# display_schematic.net
KiCad netlist of a schematic drawn in EAGLE
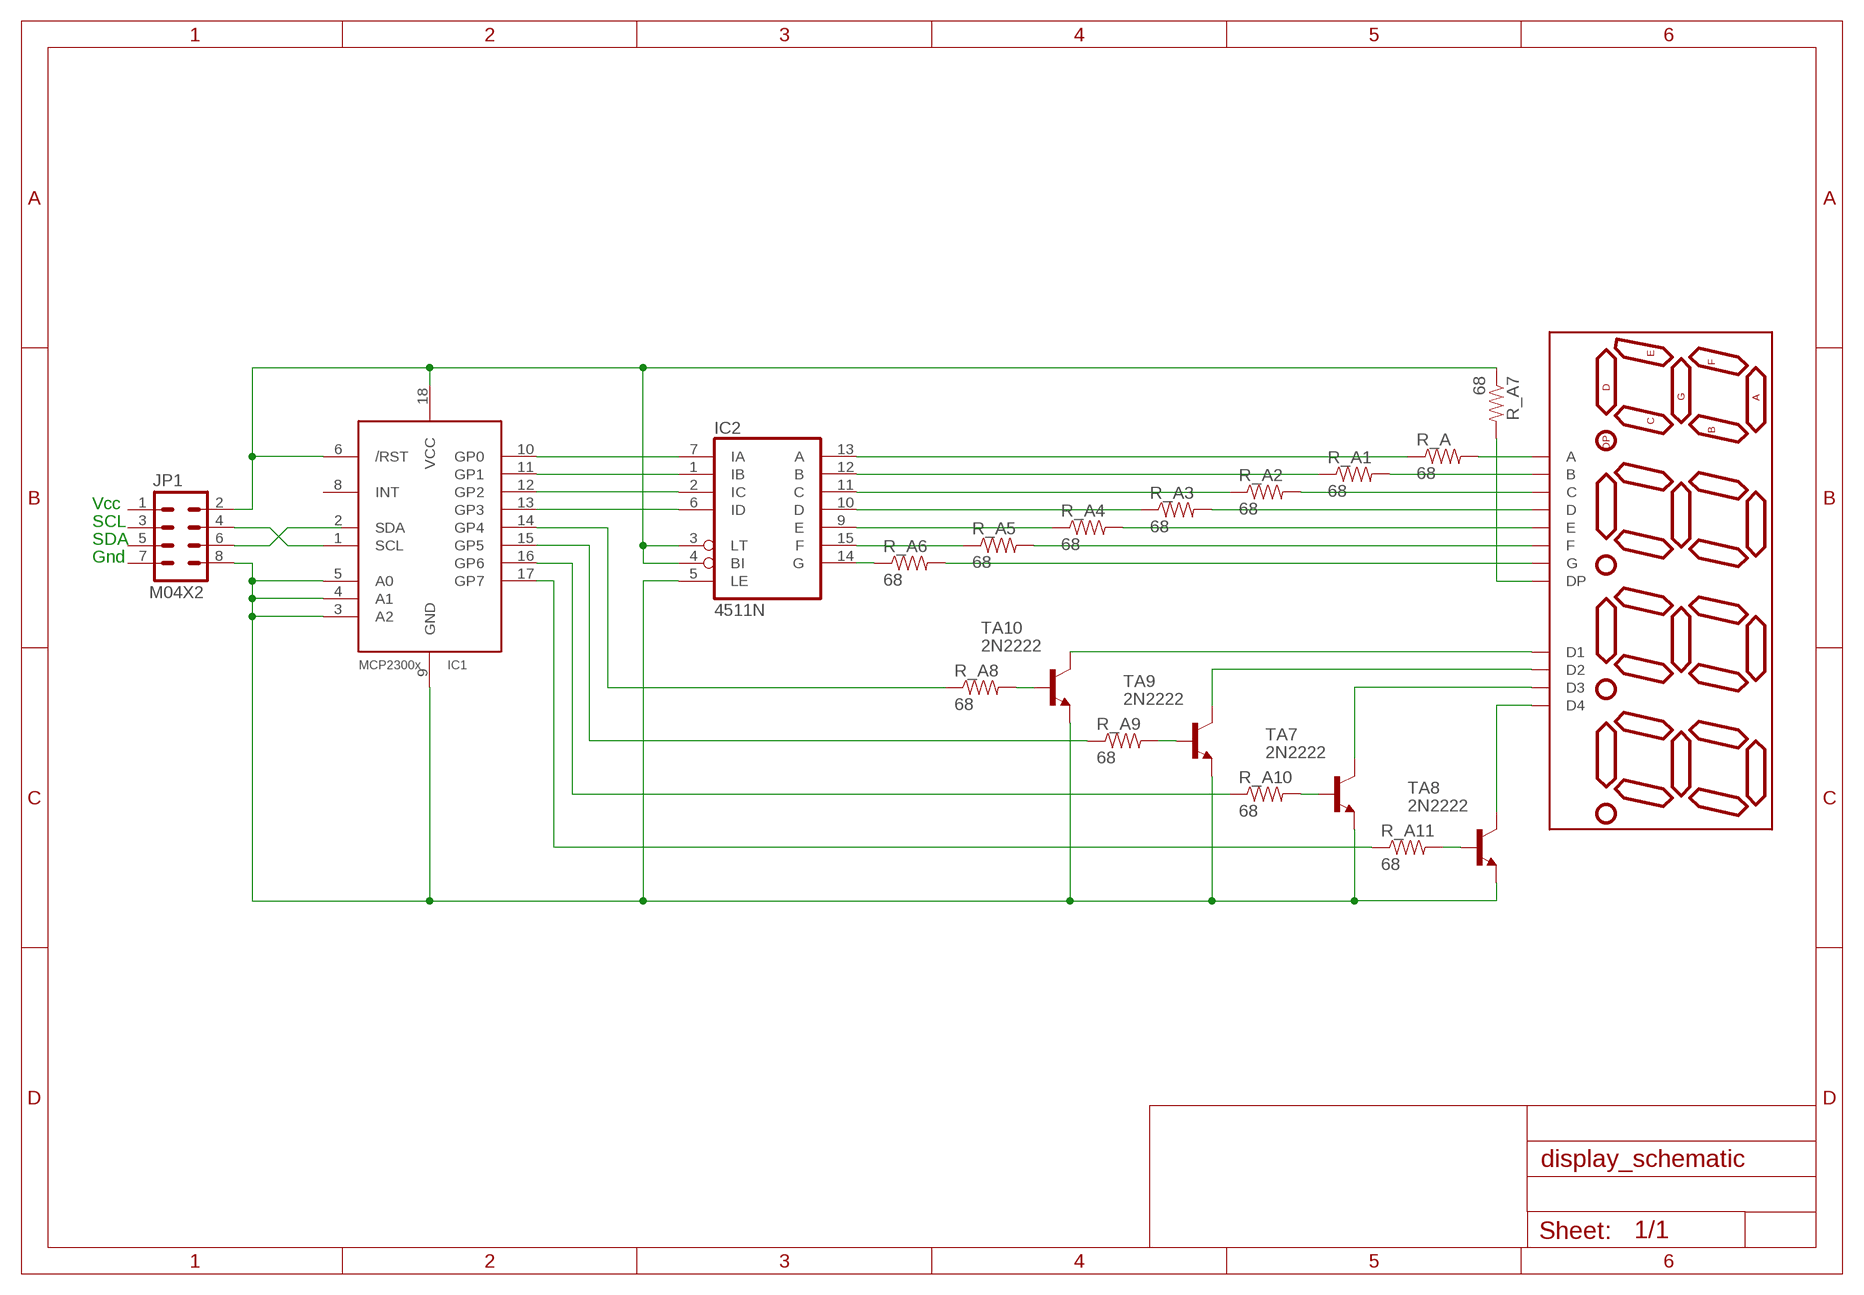
[diagram p0: schematic, sheet 1]

(export (version "E")
  (design (tool "Eeschema 10.0.6"))
  (components
    (comp (ref "DISPLAY7S4D1")
      (value "7SEG-4DIG-NEW")
      (footprint "eagle-import:7SEG-4DIG-NEW")
      (libsource (lib "eagle-import") (part "7SEG-4DIG-NEW"))
    )
    (comp (ref "IC1")
      (value "MCP2300X/P")
      (footprint "eagle-import:DIL18")
      (libsource (lib "eagle-import") (part "MCP2300X/P"))
    )
    (comp (ref "IC2")
      (value "4511N")
      (footprint "eagle-import:DIL16")
      (libsource (lib "eagle-import") (part "4511N"))
    )
    (comp (ref "JP1")
      (value "M04X2")
      (footprint "eagle-import:2X4")
      (libsource (lib "eagle-import") (part "M04X2"))
    )
    (comp (ref "R_A")
      (value "68")
      (footprint "eagle-import:AXIAL-0.3")
      (libsource (lib "eagle-import") (part "RESISTORAXIAL-0.3"))
    )
    (comp (ref "R_A1")
      (value "68")
      (footprint "eagle-import:AXIAL-0.3")
      (libsource (lib "eagle-import") (part "RESISTORAXIAL-0.3"))
    )
    (comp (ref "R_A2")
      (value "68")
      (footprint "eagle-import:AXIAL-0.3")
      (libsource (lib "eagle-import") (part "RESISTORAXIAL-0.3"))
    )
    (comp (ref "R_A3")
      (value "68")
      (footprint "eagle-import:AXIAL-0.3")
      (libsource (lib "eagle-import") (part "RESISTORAXIAL-0.3"))
    )
    (comp (ref "R_A4")
      (value "68")
      (footprint "eagle-import:AXIAL-0.3")
      (libsource (lib "eagle-import") (part "RESISTORAXIAL-0.3"))
    )
    (comp (ref "R_A5")
      (value "68")
      (footprint "eagle-import:AXIAL-0.3")
      (libsource (lib "eagle-import") (part "RESISTORAXIAL-0.3"))
    )
    (comp (ref "R_A6")
      (value "68")
      (footprint "eagle-import:AXIAL-0.3")
      (libsource (lib "eagle-import") (part "RESISTORAXIAL-0.3"))
    )
    (comp (ref "R_A7")
      (value "68")
      (footprint "eagle-import:AXIAL-0.3")
      (libsource (lib "eagle-import") (part "RESISTORAXIAL-0.3"))
    )
    (comp (ref "R_A8")
      (value "68")
      (footprint "eagle-import:AXIAL-0.3")
      (libsource (lib "eagle-import") (part "RESISTORAXIAL-0.3"))
    )
    (comp (ref "R_A9")
      (value "68")
      (footprint "eagle-import:AXIAL-0.3")
      (libsource (lib "eagle-import") (part "RESISTORAXIAL-0.3"))
    )
    (comp (ref "R_A10")
      (value "68")
      (footprint "eagle-import:AXIAL-0.3")
      (libsource (lib "eagle-import") (part "RESISTORAXIAL-0.3"))
    )
    (comp (ref "R_A11")
      (value "68")
      (footprint "eagle-import:AXIAL-0.3")
      (libsource (lib "eagle-import") (part "RESISTORAXIAL-0.3"))
    )
    (comp (ref "TA7")
      (value "2N2222")
      (footprint "eagle-import:TO92-EBC-OVAL")
      (libsource (lib "eagle-import") (part "2N2222"))
    )
    (comp (ref "TA8")
      (value "2N2222")
      (footprint "eagle-import:TO92-EBC-OVAL")
      (libsource (lib "eagle-import") (part "2N2222"))
    )
    (comp (ref "TA9")
      (value "2N2222")
      (footprint "eagle-import:TO92-EBC-OVAL")
      (libsource (lib "eagle-import") (part "2N2222"))
    )
    (comp (ref "TA10")
      (value "2N2222")
      (footprint "eagle-import:TO92-EBC-OVAL")
      (libsource (lib "eagle-import") (part "2N2222"))
    )
  )
  (nets
    (net (code "1") (name "Net-(DISPLAY7S4D1-A)") (class "Default")
      (node (ref "DISPLAY7S4D1") (pin "11") (pinfunction "A_11") (pintype "bidirectional"))
      (node (ref "R_A") (pin "P$2") (pinfunction "2_P$2") (pintype "passive"))
    )
    (net (code "2") (name "Net-(DISPLAY7S4D1-B)") (class "Default")
      (node (ref "DISPLAY7S4D1") (pin "7") (pinfunction "B_7") (pintype "bidirectional"))
      (node (ref "R_A1") (pin "P$2") (pinfunction "2_P$2") (pintype "passive"))
    )
    (net (code "3") (name "Net-(DISPLAY7S4D1-C)") (class "Default")
      (node (ref "DISPLAY7S4D1") (pin "4") (pinfunction "C_4") (pintype "bidirectional"))
      (node (ref "R_A2") (pin "P$2") (pinfunction "2_P$2") (pintype "passive"))
    )
    (net (code "4") (name "Net-(DISPLAY7S4D1-D)") (class "Default")
      (node (ref "DISPLAY7S4D1") (pin "2") (pinfunction "D_2") (pintype "bidirectional"))
      (node (ref "R_A3") (pin "P$2") (pinfunction "2_P$2") (pintype "passive"))
    )
    (net (code "5") (name "Net-(DISPLAY7S4D1-D1)") (class "Default")
      (node (ref "DISPLAY7S4D1") (pin "12") (pinfunction "D1_12") (pintype "bidirectional"))
      (node (ref "TA10") (pin "C") (pinfunction "C_C") (pintype "passive"))
    )
    (net (code "6") (name "Net-(DISPLAY7S4D1-D2)") (class "Default")
      (node (ref "DISPLAY7S4D1") (pin "9") (pinfunction "D2_9") (pintype "bidirectional"))
      (node (ref "TA9") (pin "C") (pinfunction "C_C") (pintype "passive"))
    )
    (net (code "7") (name "Net-(DISPLAY7S4D1-D3)") (class "Default")
      (node (ref "DISPLAY7S4D1") (pin "8") (pinfunction "D3_8") (pintype "bidirectional"))
      (node (ref "TA7") (pin "C") (pinfunction "C_C") (pintype "passive"))
    )
    (net (code "8") (name "Net-(DISPLAY7S4D1-D4)") (class "Default")
      (node (ref "DISPLAY7S4D1") (pin "6") (pinfunction "D4_6") (pintype "bidirectional"))
      (node (ref "TA8") (pin "C") (pinfunction "C_C") (pintype "passive"))
    )
    (net (code "9") (name "Net-(DISPLAY7S4D1-DP)") (class "Default")
      (node (ref "DISPLAY7S4D1") (pin "3") (pinfunction "DP_3") (pintype "bidirectional"))
      (node (ref "R_A7") (pin "P$2") (pinfunction "2_P$2") (pintype "passive"))
    )
    (net (code "10") (name "Net-(DISPLAY7S4D1-E)") (class "Default")
      (node (ref "DISPLAY7S4D1") (pin "1") (pinfunction "E_1") (pintype "bidirectional"))
      (node (ref "R_A4") (pin "P$2") (pinfunction "2_P$2") (pintype "passive"))
    )
    (net (code "11") (name "Net-(DISPLAY7S4D1-F)") (class "Default")
      (node (ref "DISPLAY7S4D1") (pin "10") (pinfunction "F_10") (pintype "bidirectional"))
      (node (ref "R_A5") (pin "P$2") (pinfunction "2_P$2") (pintype "passive"))
    )
    (net (code "12") (name "Net-(DISPLAY7S4D1-G)") (class "Default")
      (node (ref "DISPLAY7S4D1") (pin "5") (pinfunction "G_5") (pintype "bidirectional"))
      (node (ref "R_A6") (pin "P$2") (pinfunction "2_P$2") (pintype "passive"))
    )
    (net (code "13") (name "Net-(IC1-A0)") (class "Default")
      (node (ref "IC1") (pin "3") (pinfunction "A2_3") (pintype "input"))
      (node (ref "IC1") (pin "4") (pinfunction "A1_4") (pintype "input"))
      (node (ref "IC1") (pin "5") (pinfunction "A0_5") (pintype "input"))
      (node (ref "IC1") (pin "9") (pinfunction "GND_9") (pintype "power_in"))
      (node (ref "IC2") (pin "5") (pinfunction "LE_5") (pintype "input"))
      (node (ref "JP1") (pin "8") (pinfunction "8_8") (pintype "passive"))
      (node (ref "TA10") (pin "E") (pinfunction "E_E") (pintype "passive"))
      (node (ref "TA7") (pin "E") (pinfunction "E_E") (pintype "passive"))
      (node (ref "TA8") (pin "E") (pinfunction "E_E") (pintype "passive"))
      (node (ref "TA9") (pin "E") (pinfunction "E_E") (pintype "passive"))
    )
    (net (code "14") (name "Net-(IC1-GP0)") (class "Default")
      (node (ref "IC1") (pin "10") (pinfunction "GP0_10") (pintype "bidirectional"))
      (node (ref "IC2") (pin "7") (pinfunction "IA_7") (pintype "input"))
    )
    (net (code "15") (name "Net-(IC1-GP1)") (class "Default")
      (node (ref "IC1") (pin "11") (pinfunction "GP1_11") (pintype "bidirectional"))
      (node (ref "IC2") (pin "1") (pinfunction "IB_1") (pintype "input"))
    )
    (net (code "16") (name "Net-(IC1-GP2)") (class "Default")
      (node (ref "IC1") (pin "12") (pinfunction "GP2_12") (pintype "bidirectional"))
      (node (ref "IC2") (pin "2") (pinfunction "IC_2") (pintype "input"))
    )
    (net (code "17") (name "Net-(IC1-GP3)") (class "Default")
      (node (ref "IC1") (pin "13") (pinfunction "GP3_13") (pintype "bidirectional"))
      (node (ref "IC2") (pin "6") (pinfunction "ID_6") (pintype "input"))
    )
    (net (code "18") (name "Net-(IC1-GP4)") (class "Default")
      (node (ref "IC1") (pin "14") (pinfunction "GP4_14") (pintype "bidirectional"))
      (node (ref "R_A8") (pin "P$1") (pinfunction "1_P$1") (pintype "passive"))
    )
    (net (code "19") (name "Net-(IC1-GP5)") (class "Default")
      (node (ref "IC1") (pin "15") (pinfunction "GP5_15") (pintype "bidirectional"))
      (node (ref "R_A9") (pin "P$1") (pinfunction "1_P$1") (pintype "passive"))
    )
    (net (code "20") (name "Net-(IC1-GP6)") (class "Default")
      (node (ref "IC1") (pin "16") (pinfunction "GP6_16") (pintype "bidirectional"))
      (node (ref "R_A10") (pin "P$1") (pinfunction "1_P$1") (pintype "passive"))
    )
    (net (code "21") (name "Net-(IC1-GP7)") (class "Default")
      (node (ref "IC1") (pin "17") (pinfunction "GP7_17") (pintype "bidirectional"))
      (node (ref "R_A11") (pin "P$1") (pinfunction "1_P$1") (pintype "passive"))
    )
    (net (code "22") (name "Net-(IC1-SCL)") (class "Default")
      (node (ref "IC1") (pin "1") (pinfunction "SCL_1") (pintype "bidirectional"))
      (node (ref "JP1") (pin "4") (pinfunction "4_4") (pintype "passive"))
    )
    (net (code "23") (name "Net-(IC1-VCC)") (class "Default")
      (node (ref "IC1") (pin "18") (pinfunction "VCC_18") (pintype "power_in"))
      (node (ref "IC1") (pin "6") (pinfunction "/RST_6") (pintype "input"))
      (node (ref "IC2") (pin "3") (pinfunction "LT_3") (pintype "input"))
      (node (ref "IC2") (pin "4") (pinfunction "BI_4") (pintype "input"))
      (node (ref "JP1") (pin "2") (pinfunction "2_2") (pintype "passive"))
      (node (ref "R_A7") (pin "P$1") (pinfunction "1_P$1") (pintype "passive"))
    )
    (net (code "24") (name "Net-(IC2A-A)") (class "Default")
      (node (ref "IC2") (pin "13") (pinfunction "A_13") (pintype "output"))
      (node (ref "R_A") (pin "P$1") (pinfunction "1_P$1") (pintype "passive"))
    )
    (net (code "25") (name "Net-(IC2A-B)") (class "Default")
      (node (ref "IC2") (pin "12") (pinfunction "B_12") (pintype "output"))
      (node (ref "R_A1") (pin "P$1") (pinfunction "1_P$1") (pintype "passive"))
    )
    (net (code "26") (name "Net-(IC2A-C)") (class "Default")
      (node (ref "IC2") (pin "11") (pinfunction "C_11") (pintype "output"))
      (node (ref "R_A2") (pin "P$1") (pinfunction "1_P$1") (pintype "passive"))
    )
    (net (code "27") (name "Net-(IC2A-D)") (class "Default")
      (node (ref "IC2") (pin "10") (pinfunction "D_10") (pintype "output"))
      (node (ref "R_A3") (pin "P$1") (pinfunction "1_P$1") (pintype "passive"))
    )
    (net (code "28") (name "Net-(IC2A-E)") (class "Default")
      (node (ref "IC2") (pin "9") (pinfunction "E_9") (pintype "output"))
      (node (ref "R_A4") (pin "P$1") (pinfunction "1_P$1") (pintype "passive"))
    )
    (net (code "29") (name "Net-(IC2A-F)") (class "Default")
      (node (ref "IC2") (pin "15") (pinfunction "F_15") (pintype "output"))
      (node (ref "R_A5") (pin "P$1") (pinfunction "1_P$1") (pintype "passive"))
    )
    (net (code "30") (name "Net-(IC2A-G)") (class "Default")
      (node (ref "IC2") (pin "14") (pinfunction "G_14") (pintype "output"))
      (node (ref "R_A6") (pin "P$1") (pinfunction "1_P$1") (pintype "passive"))
    )
    (net (code "31") (name "Net-(R_A8-2)") (class "Default")
      (node (ref "R_A8") (pin "P$2") (pinfunction "2_P$2") (pintype "passive"))
      (node (ref "TA10") (pin "B") (pinfunction "B_B") (pintype "passive"))
    )
    (net (code "32") (name "Net-(R_A9-2)") (class "Default")
      (node (ref "R_A9") (pin "P$2") (pinfunction "2_P$2") (pintype "passive"))
      (node (ref "TA9") (pin "B") (pinfunction "B_B") (pintype "passive"))
    )
    (net (code "33") (name "Net-(R_A10-2)") (class "Default")
      (node (ref "R_A10") (pin "P$2") (pinfunction "2_P$2") (pintype "passive"))
      (node (ref "TA7") (pin "B") (pinfunction "B_B") (pintype "passive"))
    )
    (net (code "34") (name "Net-(R_A11-2)") (class "Default")
      (node (ref "R_A11") (pin "P$2") (pinfunction "2_P$2") (pintype "passive"))
      (node (ref "TA8") (pin "B") (pinfunction "B_B") (pintype "passive"))
    )
    (net (code "35") (name "unconnected-(IC1-INT-Pad8)") (class "Default")
      (node (ref "IC1") (pin "8") (pinfunction "INT_8") (pintype "output"))
    )
    (net (code "36") (name "unconnected-(IC1-SDA-Pad2)") (class "Default")
      (node (ref "IC1") (pin "2") (pinfunction "SDA_2") (pintype "bidirectional"))
    )
    (net (code "37") (name "unconnected-(JP1-Pad1)") (class "Default")
      (node (ref "JP1") (pin "1") (pinfunction "1_1") (pintype "passive"))
    )
    (net (code "38") (name "unconnected-(JP1-Pad3)") (class "Default")
      (node (ref "JP1") (pin "3") (pinfunction "3_3") (pintype "passive"))
    )
    (net (code "39") (name "unconnected-(JP1-Pad5)") (class "Default")
      (node (ref "JP1") (pin "5") (pinfunction "5_5") (pintype "passive"))
    )
    (net (code "40") (name "unconnected-(JP1-Pad6)") (class "Default")
      (node (ref "JP1") (pin "6") (pinfunction "6_6") (pintype "passive"))
    )
    (net (code "41") (name "unconnected-(JP1-Pad7)") (class "Default")
      (node (ref "JP1") (pin "7") (pinfunction "7_7") (pintype "passive"))
    )
  )
)
